# Ring_opto_interface_v2_1.net
KiCad netlist of a schematic drawn in EAGLE
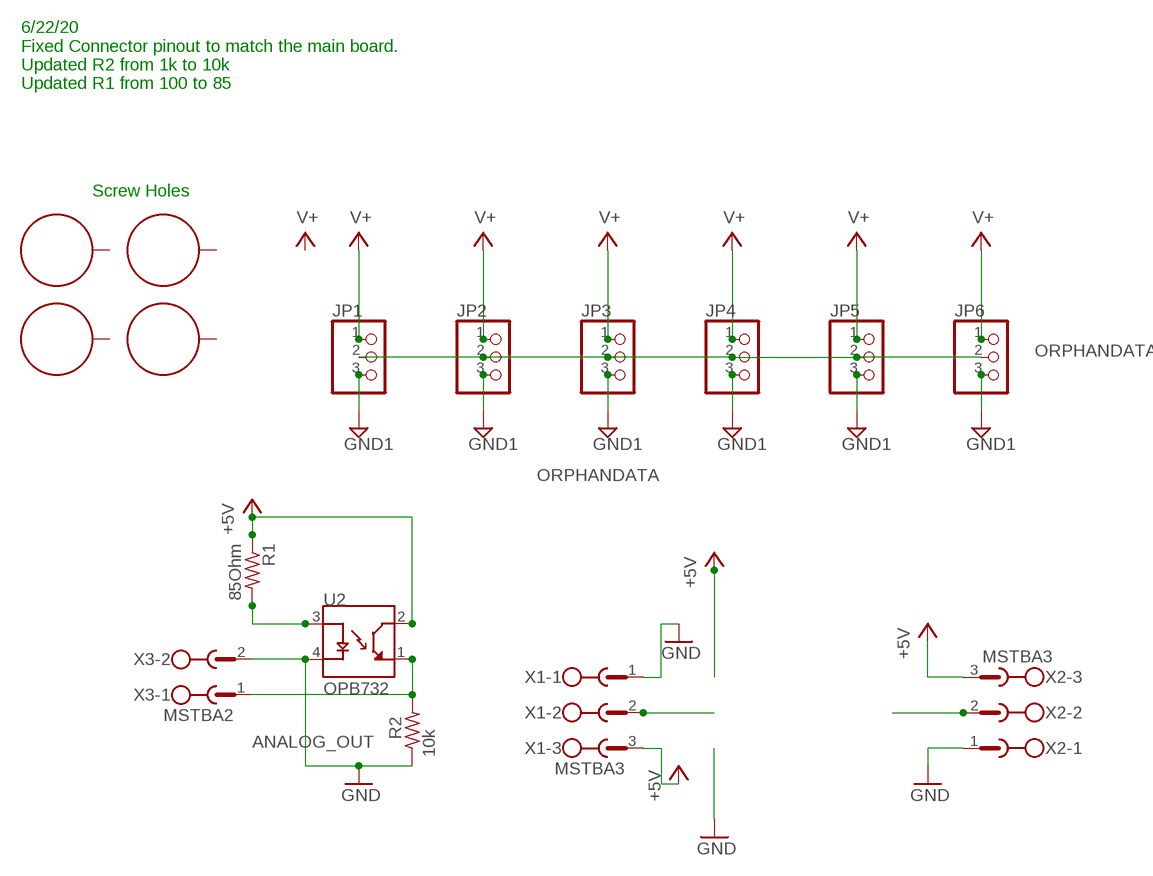
[diagram p0: schematic, sheet 1]

(export (version "E")
  (design (tool "Eeschema 10.0.6"))
  (components
    (comp (ref "H1")
      (value "STANDOFF_ELECTRICAL5-32")
      (footprint "eagle-import:STANDOFF_ELECTRICAL_5_32")
      (libsource (lib "eagle-import") (part "STANDOFF_ELECTRICAL5-32"))
    )
    (comp (ref "H2")
      (value "STANDOFF_ELECTRICAL5-32")
      (footprint "eagle-import:STANDOFF_ELECTRICAL_5_32")
      (libsource (lib "eagle-import") (part "STANDOFF_ELECTRICAL5-32"))
    )
    (comp (ref "H3")
      (value "STANDOFF_ELECTRICAL5-32")
      (footprint "eagle-import:STANDOFF_ELECTRICAL_5_32")
      (libsource (lib "eagle-import") (part "STANDOFF_ELECTRICAL5-32"))
    )
    (comp (ref "H4")
      (value "STANDOFF_ELECTRICAL5-32")
      (footprint "eagle-import:STANDOFF_ELECTRICAL_5_32")
      (libsource (lib "eagle-import") (part "STANDOFF_ELECTRICAL5-32"))
    )
    (comp (ref "JP1")
      (value "PINHD-1X3CB")
      (footprint "eagle-import:1X03-CLEANBIG")
      (libsource (lib "eagle-import") (part "PINHD-1X3CB"))
    )
    (comp (ref "JP2")
      (value "PINHD-1X3CB")
      (footprint "eagle-import:1X03-CLEANBIG")
      (libsource (lib "eagle-import") (part "PINHD-1X3CB"))
    )
    (comp (ref "JP3")
      (value "PINHD-1X3CB")
      (footprint "eagle-import:1X03-CLEANBIG")
      (libsource (lib "eagle-import") (part "PINHD-1X3CB"))
    )
    (comp (ref "JP4")
      (value "PINHD-1X3CB")
      (footprint "eagle-import:1X03-CLEANBIG")
      (libsource (lib "eagle-import") (part "PINHD-1X3CB"))
    )
    (comp (ref "JP5")
      (value "PINHD-1X3CB")
      (footprint "eagle-import:1X03-CLEANBIG")
      (libsource (lib "eagle-import") (part "PINHD-1X3CB"))
    )
    (comp (ref "JP6")
      (value "PINHD-1X3CB")
      (footprint "eagle-import:1X03-CLEANBIG")
      (libsource (lib "eagle-import") (part "PINHD-1X3CB"))
    )
    (comp (ref "R1")
      (value "85Ohm")
      (footprint "eagle-import:RESAD1176W63L850D250B")
      (libsource (lib "eagle-import") (part "R-USAXIAL-11.7MM-PITCH_"))
    )
    (comp (ref "R2")
      (value "10k")
      (footprint "eagle-import:RESAD1176W63L850D250B")
      (libsource (lib "eagle-import") (part "R-USAXIAL-11.7MM-PITCH_"))
    )
    (comp (ref "U2")
      (value "OPB732")
      (footprint "eagle-import:OPTO_OPB732")
      (fields (field (name "MF") "TT Electronics/Optek"))
      (libsource (lib "eagle-import") (part "OPB732"))
    )
    (comp (ref "X1")
      (value "MSTBA3")
      (footprint "eagle-import:MSTBA3")
      (fields (field (name "MF") "FARNELL") (field (name "MPN") "1757255"))
      (libsource (lib "eagle-import") (part "MSTBA3"))
    )
    (comp (ref "X2")
      (value "MSTBA3")
      (footprint "eagle-import:MSTBA3")
      (fields (field (name "MF") "FARNELL") (field (name "MPN") "1757255"))
      (libsource (lib "eagle-import") (part "MSTBA3"))
    )
    (comp (ref "X3")
      (value "MSTBA2")
      (footprint "eagle-import:MSTBA2")
      (fields (field (name "MF") "FARNELL") (field (name "MPN") "1757242"))
      (libsource (lib "eagle-import") (part "MSTBA2"))
    )
  )
  (nets
    (net (code "1") (name "+5V") (class "Default")
      (node (ref "R1") (pin "1") (pinfunction "1_1") (pintype "passive"))
      (node (ref "U2") (pin "2") (pinfunction "CT_2") (pintype "passive"))
      (node (ref "X1") (pin "3") (pinfunction "1_3") (pintype "passive"))
      (node (ref "X2") (pin "3") (pinfunction "1_3") (pintype "passive"))
    )
    (net (code "2") (name "/ANALOG_OUT") (class "Default")
      (node (ref "R2") (pin "2") (pinfunction "2_2") (pintype "passive"))
      (node (ref "U2") (pin "1") (pinfunction "ET_1") (pintype "passive"))
      (node (ref "X3") (pin "1") (pinfunction "1_1") (pintype "passive"))
    )
    (net (code "3") (name "/ORPHANDATA") (class "Default")
      (node (ref "JP1") (pin "2") (pinfunction "2_2") (pintype "passive"))
      (node (ref "JP2") (pin "2") (pinfunction "2_2") (pintype "passive"))
      (node (ref "JP3") (pin "2") (pinfunction "2_2") (pintype "passive"))
      (node (ref "JP4") (pin "2") (pinfunction "2_2") (pintype "passive"))
      (node (ref "JP5") (pin "2") (pinfunction "2_2") (pintype "passive"))
      (node (ref "JP6") (pin "2") (pinfunction "2_2") (pintype "passive"))
    )
    (net (code "4") (name "GND") (class "Default")
      (node (ref "R2") (pin "1") (pinfunction "1_1") (pintype "passive"))
      (node (ref "U2") (pin "4") (pinfunction "C_4") (pintype "passive"))
      (node (ref "X1") (pin "1") (pinfunction "1_1") (pintype "passive"))
      (node (ref "X2") (pin "1") (pinfunction "1_1") (pintype "passive"))
      (node (ref "X3") (pin "2") (pinfunction "1_2") (pintype "passive"))
    )
    (net (code "5") (name "GND1") (class "Default")
      (node (ref "JP1") (pin "3") (pinfunction "3_3") (pintype "passive"))
      (node (ref "JP2") (pin "3") (pinfunction "3_3") (pintype "passive"))
      (node (ref "JP3") (pin "3") (pinfunction "3_3") (pintype "passive"))
      (node (ref "JP4") (pin "3") (pinfunction "3_3") (pintype "passive"))
      (node (ref "JP5") (pin "3") (pinfunction "3_3") (pintype "passive"))
      (node (ref "JP6") (pin "3") (pinfunction "3_3") (pintype "passive"))
    )
    (net (code "6") (name "Net-(U2-A)") (class "Default")
      (node (ref "R1") (pin "2") (pinfunction "2_2") (pintype "passive"))
      (node (ref "U2") (pin "3") (pinfunction "A_3") (pintype "passive"))
    )
    (net (code "7") (name "V+") (class "Default")
      (node (ref "JP1") (pin "1") (pinfunction "1_1") (pintype "passive"))
      (node (ref "JP2") (pin "1") (pinfunction "1_1") (pintype "passive"))
      (node (ref "JP3") (pin "1") (pinfunction "1_1") (pintype "passive"))
      (node (ref "JP4") (pin "1") (pinfunction "1_1") (pintype "passive"))
      (node (ref "JP5") (pin "1") (pinfunction "1_1") (pintype "passive"))
      (node (ref "JP6") (pin "1") (pinfunction "1_1") (pintype "passive"))
    )
    (net (code "8") (name "unconnected-(H1-P$1-PadP1)") (class "Default")
      (node (ref "H1") (pin "P1") (pinfunction "P$1_P1") (pintype "bidirectional"))
    )
    (net (code "9") (name "unconnected-(H2-P$1-PadP1)") (class "Default")
      (node (ref "H2") (pin "P1") (pinfunction "P$1_P1") (pintype "bidirectional"))
    )
    (net (code "10") (name "unconnected-(H3-P$1-PadP1)") (class "Default")
      (node (ref "H3") (pin "P1") (pinfunction "P$1_P1") (pintype "bidirectional"))
    )
    (net (code "11") (name "unconnected-(H4-P$1-PadP1)") (class "Default")
      (node (ref "H4") (pin "P1") (pinfunction "P$1_P1") (pintype "bidirectional"))
    )
    (net (code "12") (name "unconnected-(X1B-1-Pad2)") (class "Default")
      (node (ref "X1") (pin "2") (pinfunction "1_2") (pintype "passive"))
    )
    (net (code "13") (name "unconnected-(X2B-1-Pad2)") (class "Default")
      (node (ref "X2") (pin "2") (pinfunction "1_2") (pintype "passive"))
    )
  )
)
